# DriversBoard.net
KiCad netlist of a schematic drawn in Altium Designer
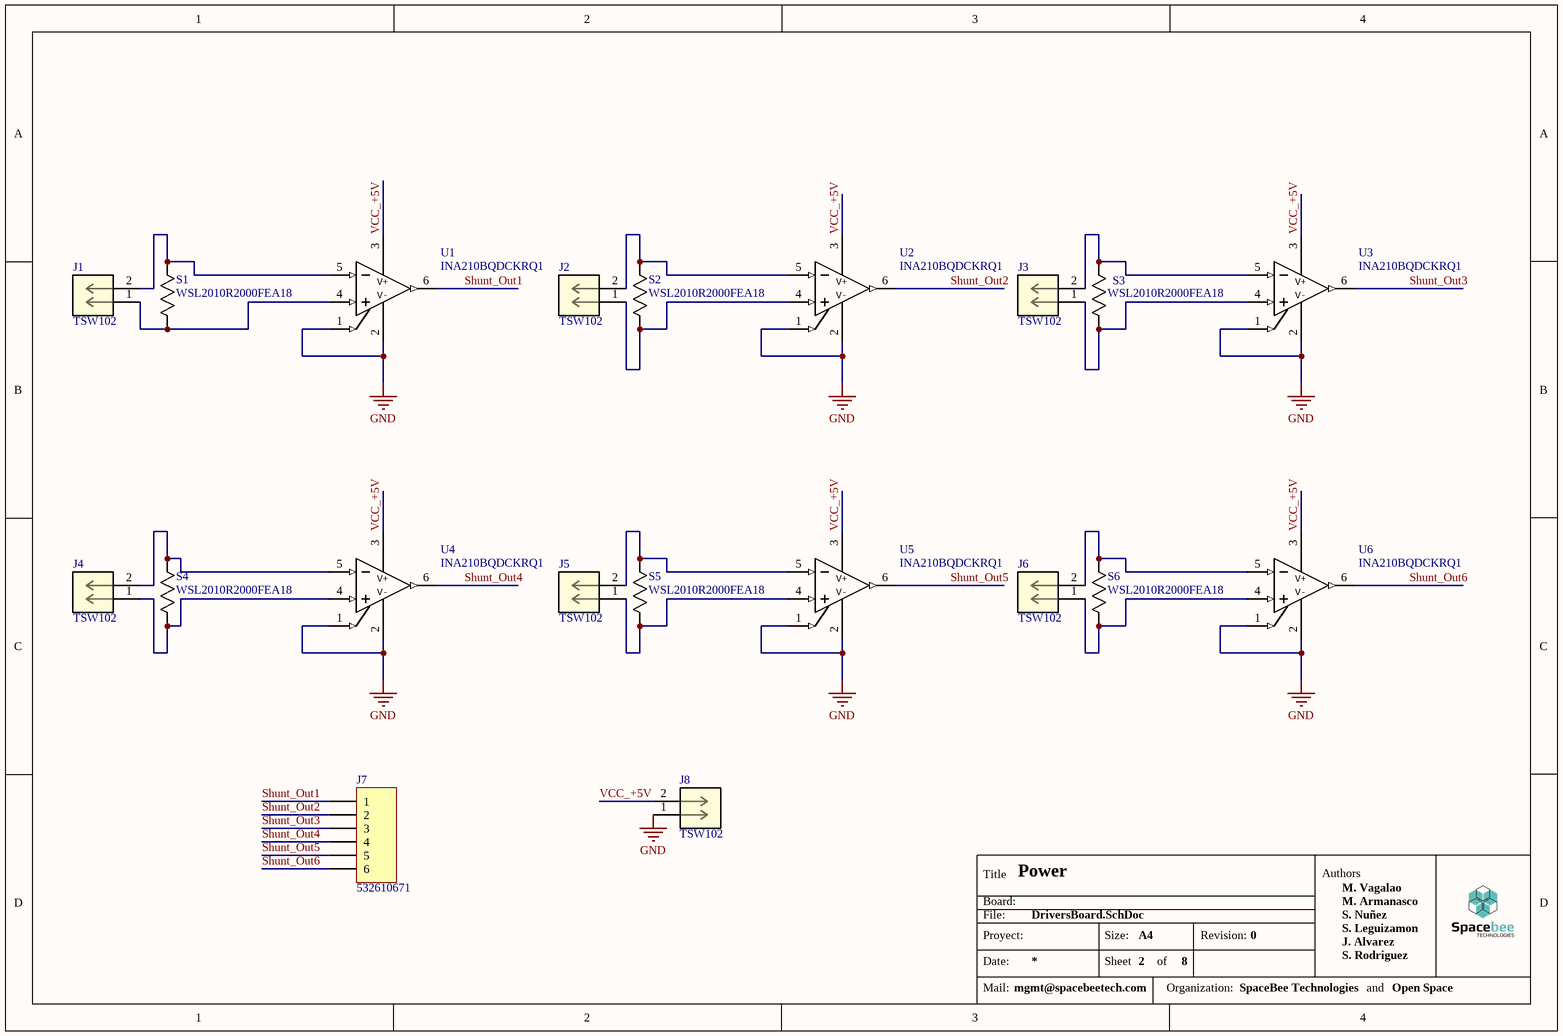
[diagram p0: DriversBoard.SchDoc]

(export (version "E")
  (design (tool "Eeschema 10.0.6"))
  (components
    (comp (ref "J1")
      (value "TSW102")
      (footprint "MOLEX_53261-0271")
      (libsource (lib "SpaceBee") (part "TSW102"))
    )
    (comp (ref "J2")
      (value "TSW102")
      (footprint "MOLEX_53261-0271")
      (libsource (lib "SpaceBee") (part "TSW102"))
    )
    (comp (ref "J3")
      (value "TSW102")
      (footprint "MOLEX_53261-0271")
      (libsource (lib "SpaceBee") (part "TSW102"))
    )
    (comp (ref "J4")
      (value "TSW102")
      (footprint "MOLEX_53261-0271")
      (libsource (lib "SpaceBee") (part "TSW102"))
    )
    (comp (ref "J5")
      (value "TSW102")
      (footprint "MOLEX_53261-0271")
      (libsource (lib "SpaceBee") (part "TSW102"))
    )
    (comp (ref "J6")
      (value "TSW102")
      (footprint "MOLEX_53261-0271")
      (libsource (lib "SpaceBee") (part "TSW102"))
    )
    (comp (ref "J7")
      (value "532610671")
      (footprint "MOLEX_532610671")
      (fields (field (name "PUBLISHER") "Altium Limited"))
      (libsource (lib "SpaceBee") (part "532610671"))
    )
    (comp (ref "J8") (value "TSW102") (footprint "MOLEX_53261-0271") (libsource (lib "") (part "TSW102_1")))
    (comp (ref "S1")
      (value "WSL2010R2000FEA18")
      (footprint "RC2010N_VIS-L")
      (description "No Description Available")
      (fields (field (name "COPYRIGHT") "Copyright (C) 2022 Ultra Librarian. All rights reserved."))
      (libsource (lib "SpaceBee") (part "WSL2010R2000FEA18"))
    )
    (comp (ref "S2")
      (value "WSL2010R2000FEA18")
      (footprint "RC2010N_VIS-L")
      (description "No Description Available")
      (fields (field (name "COPYRIGHT") "Copyright (C) 2022 Ultra Librarian. All rights reserved."))
      (libsource (lib "SpaceBee") (part "WSL2010R2000FEA18"))
    )
    (comp (ref "S3")
      (value "WSL2010R2000FEA18")
      (footprint "RC2010N_VIS-L")
      (description "No Description Available")
      (fields (field (name "COPYRIGHT") "Copyright (C) 2022 Ultra Librarian. All rights reserved."))
      (libsource (lib "SpaceBee") (part "WSL2010R2000FEA18"))
    )
    (comp (ref "S4")
      (value "WSL2010R2000FEA18")
      (footprint "RC2010N_VIS-L")
      (description "No Description Available")
      (fields (field (name "COPYRIGHT") "Copyright (C) 2022 Ultra Librarian. All rights reserved."))
      (libsource (lib "SpaceBee") (part "WSL2010R2000FEA18"))
    )
    (comp (ref "S5")
      (value "WSL2010R2000FEA18")
      (footprint "RC2010N_VIS-L")
      (description "No Description Available")
      (fields (field (name "COPYRIGHT") "Copyright (C) 2022 Ultra Librarian. All rights reserved."))
      (libsource (lib "SpaceBee") (part "WSL2010R2000FEA18"))
    )
    (comp (ref "S6")
      (value "WSL2010R2000FEA18")
      (footprint "RC2010N_VIS-L")
      (description "No Description Available")
      (fields (field (name "COPYRIGHT") "Copyright (C) 2022 Ultra Librarian. All rights reserved."))
      (libsource (lib "SpaceBee") (part "WSL2010R2000FEA18"))
    )
    (comp (ref "U1")
      (value "INA210BQDCKRQ1")
      (footprint "INA210BQDCKRQ1")
      (fields (field (name "PART NUMBER") "296-44263-2-ND"))
      (libsource (lib "SpaceBee") (part "INA210BQDCKRQ1"))
    )
    (comp (ref "U2")
      (value "INA210BQDCKRQ1")
      (footprint "INA210BQDCKRQ1")
      (fields (field (name "PART NUMBER") "296-44263-2-ND"))
      (libsource (lib "SpaceBee") (part "INA210BQDCKRQ1"))
    )
    (comp (ref "U3")
      (value "INA210BQDCKRQ1")
      (footprint "INA210BQDCKRQ1")
      (fields (field (name "PART NUMBER") "296-44263-2-ND"))
      (libsource (lib "SpaceBee") (part "INA210BQDCKRQ1"))
    )
    (comp (ref "U4")
      (value "INA210BQDCKRQ1")
      (footprint "INA210BQDCKRQ1")
      (fields (field (name "PART NUMBER") "296-44263-2-ND"))
      (libsource (lib "SpaceBee") (part "INA210BQDCKRQ1"))
    )
    (comp (ref "U5")
      (value "INA210BQDCKRQ1")
      (footprint "INA210BQDCKRQ1")
      (fields (field (name "PART NUMBER") "296-44263-2-ND"))
      (libsource (lib "SpaceBee") (part "INA210BQDCKRQ1"))
    )
    (comp (ref "U6")
      (value "INA210BQDCKRQ1")
      (footprint "INA210BQDCKRQ1")
      (fields (field (name "PART NUMBER") "296-44263-2-ND"))
      (libsource (lib "SpaceBee") (part "INA210BQDCKRQ1"))
    )
  )
  (nets
    (net (code "1") (name "/Shunt_Out1") (class "Default")
      (node (ref "J7") (pin "1") (pinfunction "1_1") (pintype "passive"))
      (node (ref "U1") (pin "6") (pinfunction "OUT_6") (pintype "output"))
    )
    (net (code "2") (name "/Shunt_Out2") (class "Default")
      (node (ref "J7") (pin "2") (pinfunction "2_2") (pintype "passive"))
      (node (ref "U2") (pin "6") (pinfunction "OUT_6") (pintype "output"))
    )
    (net (code "3") (name "/Shunt_Out3") (class "Default")
      (node (ref "J7") (pin "3") (pinfunction "3_3") (pintype "passive"))
      (node (ref "U3") (pin "6") (pinfunction "OUT_6") (pintype "output"))
    )
    (net (code "4") (name "/Shunt_Out4") (class "Default")
      (node (ref "J7") (pin "4") (pinfunction "4_4") (pintype "passive"))
      (node (ref "U4") (pin "6") (pinfunction "OUT_6") (pintype "output"))
    )
    (net (code "5") (name "/Shunt_Out5") (class "Default")
      (node (ref "J7") (pin "5") (pinfunction "5_5") (pintype "passive"))
      (node (ref "U5") (pin "6") (pinfunction "OUT_6") (pintype "output"))
    )
    (net (code "6") (name "/Shunt_Out6") (class "Default")
      (node (ref "J7") (pin "6") (pinfunction "6_6") (pintype "passive"))
      (node (ref "U6") (pin "6") (pinfunction "OUT_6") (pintype "output"))
    )
    (net (code "7") (name "/VCC_+5V") (class "Default")
      (node (ref "J8") (pin "2") (pinfunction "2_2") (pintype "passive"))
      (node (ref "U1") (pin "3") (pinfunction "V+_3") (pintype "power_in"))
      (node (ref "U2") (pin "3") (pinfunction "V+_3") (pintype "power_in"))
      (node (ref "U3") (pin "3") (pinfunction "V+_3") (pintype "power_in"))
      (node (ref "U4") (pin "3") (pinfunction "V+_3") (pintype "power_in"))
      (node (ref "U5") (pin "3") (pinfunction "V+_3") (pintype "power_in"))
      (node (ref "U6") (pin "3") (pinfunction "V+_3") (pintype "power_in"))
    )
    (net (code "8") (name "GND") (class "Default")
      (node (ref "J8") (pin "1") (pinfunction "1_1") (pintype "passive"))
      (node (ref "U1") (pin "1") (pinfunction "REF_1") (pintype "input"))
      (node (ref "U1") (pin "2") (pinfunction "GND_2") (pintype "power_in"))
      (node (ref "U2") (pin "1") (pinfunction "REF_1") (pintype "input"))
      (node (ref "U2") (pin "2") (pinfunction "GND_2") (pintype "power_in"))
      (node (ref "U3") (pin "1") (pinfunction "REF_1") (pintype "input"))
      (node (ref "U3") (pin "2") (pinfunction "GND_2") (pintype "power_in"))
      (node (ref "U4") (pin "1") (pinfunction "REF_1") (pintype "input"))
      (node (ref "U4") (pin "2") (pinfunction "GND_2") (pintype "power_in"))
      (node (ref "U5") (pin "1") (pinfunction "REF_1") (pintype "input"))
      (node (ref "U5") (pin "2") (pinfunction "GND_2") (pintype "power_in"))
      (node (ref "U6") (pin "1") (pinfunction "REF_1") (pintype "input"))
      (node (ref "U6") (pin "2") (pinfunction "GND_2") (pintype "power_in"))
    )
    (net (code "9") (name "Net-(U1-IN+)") (class "Default")
      (node (ref "J1") (pin "1") (pinfunction "1_1") (pintype "passive"))
      (node (ref "S1") (pin "2") (pinfunction "2_2") (pintype "passive"))
      (node (ref "U1") (pin "4") (pinfunction "IN+_4") (pintype "input"))
    )
    (net (code "10") (name "Net-(U1-IN-)") (class "Default")
      (node (ref "J1") (pin "2") (pinfunction "2_2") (pintype "passive"))
      (node (ref "S1") (pin "1") (pinfunction "1_1") (pintype "passive"))
      (node (ref "U1") (pin "5") (pinfunction "IN-_5") (pintype "input"))
    )
    (net (code "11") (name "Net-(U2-IN+)") (class "Default")
      (node (ref "J2") (pin "1") (pinfunction "1_1") (pintype "passive"))
      (node (ref "S2") (pin "2") (pinfunction "2_2") (pintype "passive"))
      (node (ref "U2") (pin "4") (pinfunction "IN+_4") (pintype "input"))
    )
    (net (code "12") (name "Net-(U2-IN-)") (class "Default")
      (node (ref "J2") (pin "2") (pinfunction "2_2") (pintype "passive"))
      (node (ref "S2") (pin "1") (pinfunction "1_1") (pintype "passive"))
      (node (ref "U2") (pin "5") (pinfunction "IN-_5") (pintype "input"))
    )
    (net (code "13") (name "Net-(U3-IN+)") (class "Default")
      (node (ref "J3") (pin "1") (pinfunction "1_1") (pintype "passive"))
      (node (ref "S3") (pin "2") (pinfunction "2_2") (pintype "passive"))
      (node (ref "U3") (pin "4") (pinfunction "IN+_4") (pintype "input"))
    )
    (net (code "14") (name "Net-(U3-IN-)") (class "Default")
      (node (ref "J3") (pin "2") (pinfunction "2_2") (pintype "passive"))
      (node (ref "S3") (pin "1") (pinfunction "1_1") (pintype "passive"))
      (node (ref "U3") (pin "5") (pinfunction "IN-_5") (pintype "input"))
    )
    (net (code "15") (name "Net-(U4-IN+)") (class "Default")
      (node (ref "J4") (pin "1") (pinfunction "1_1") (pintype "passive"))
      (node (ref "S4") (pin "2") (pinfunction "2_2") (pintype "passive"))
      (node (ref "U4") (pin "4") (pinfunction "IN+_4") (pintype "input"))
    )
    (net (code "16") (name "Net-(U4-IN-)") (class "Default")
      (node (ref "J4") (pin "2") (pinfunction "2_2") (pintype "passive"))
      (node (ref "S4") (pin "1") (pinfunction "1_1") (pintype "passive"))
      (node (ref "U4") (pin "5") (pinfunction "IN-_5") (pintype "input"))
    )
    (net (code "17") (name "Net-(U5-IN+)") (class "Default")
      (node (ref "J5") (pin "1") (pinfunction "1_1") (pintype "passive"))
      (node (ref "S5") (pin "2") (pinfunction "2_2") (pintype "passive"))
      (node (ref "U5") (pin "4") (pinfunction "IN+_4") (pintype "input"))
    )
    (net (code "18") (name "Net-(U5-IN-)") (class "Default")
      (node (ref "J5") (pin "2") (pinfunction "2_2") (pintype "passive"))
      (node (ref "S5") (pin "1") (pinfunction "1_1") (pintype "passive"))
      (node (ref "U5") (pin "5") (pinfunction "IN-_5") (pintype "input"))
    )
    (net (code "19") (name "Net-(U6-IN+)") (class "Default")
      (node (ref "J6") (pin "1") (pinfunction "1_1") (pintype "passive"))
      (node (ref "S6") (pin "2") (pinfunction "2_2") (pintype "passive"))
      (node (ref "U6") (pin "4") (pinfunction "IN+_4") (pintype "input"))
    )
    (net (code "20") (name "Net-(U6-IN-)") (class "Default")
      (node (ref "J6") (pin "2") (pinfunction "2_2") (pintype "passive"))
      (node (ref "S6") (pin "1") (pinfunction "1_1") (pintype "passive"))
      (node (ref "U6") (pin "5") (pinfunction "IN-_5") (pintype "input"))
    )
  )
)
